# CoinLogger.net
KiCad netlist of a schematic drawn in EAGLE
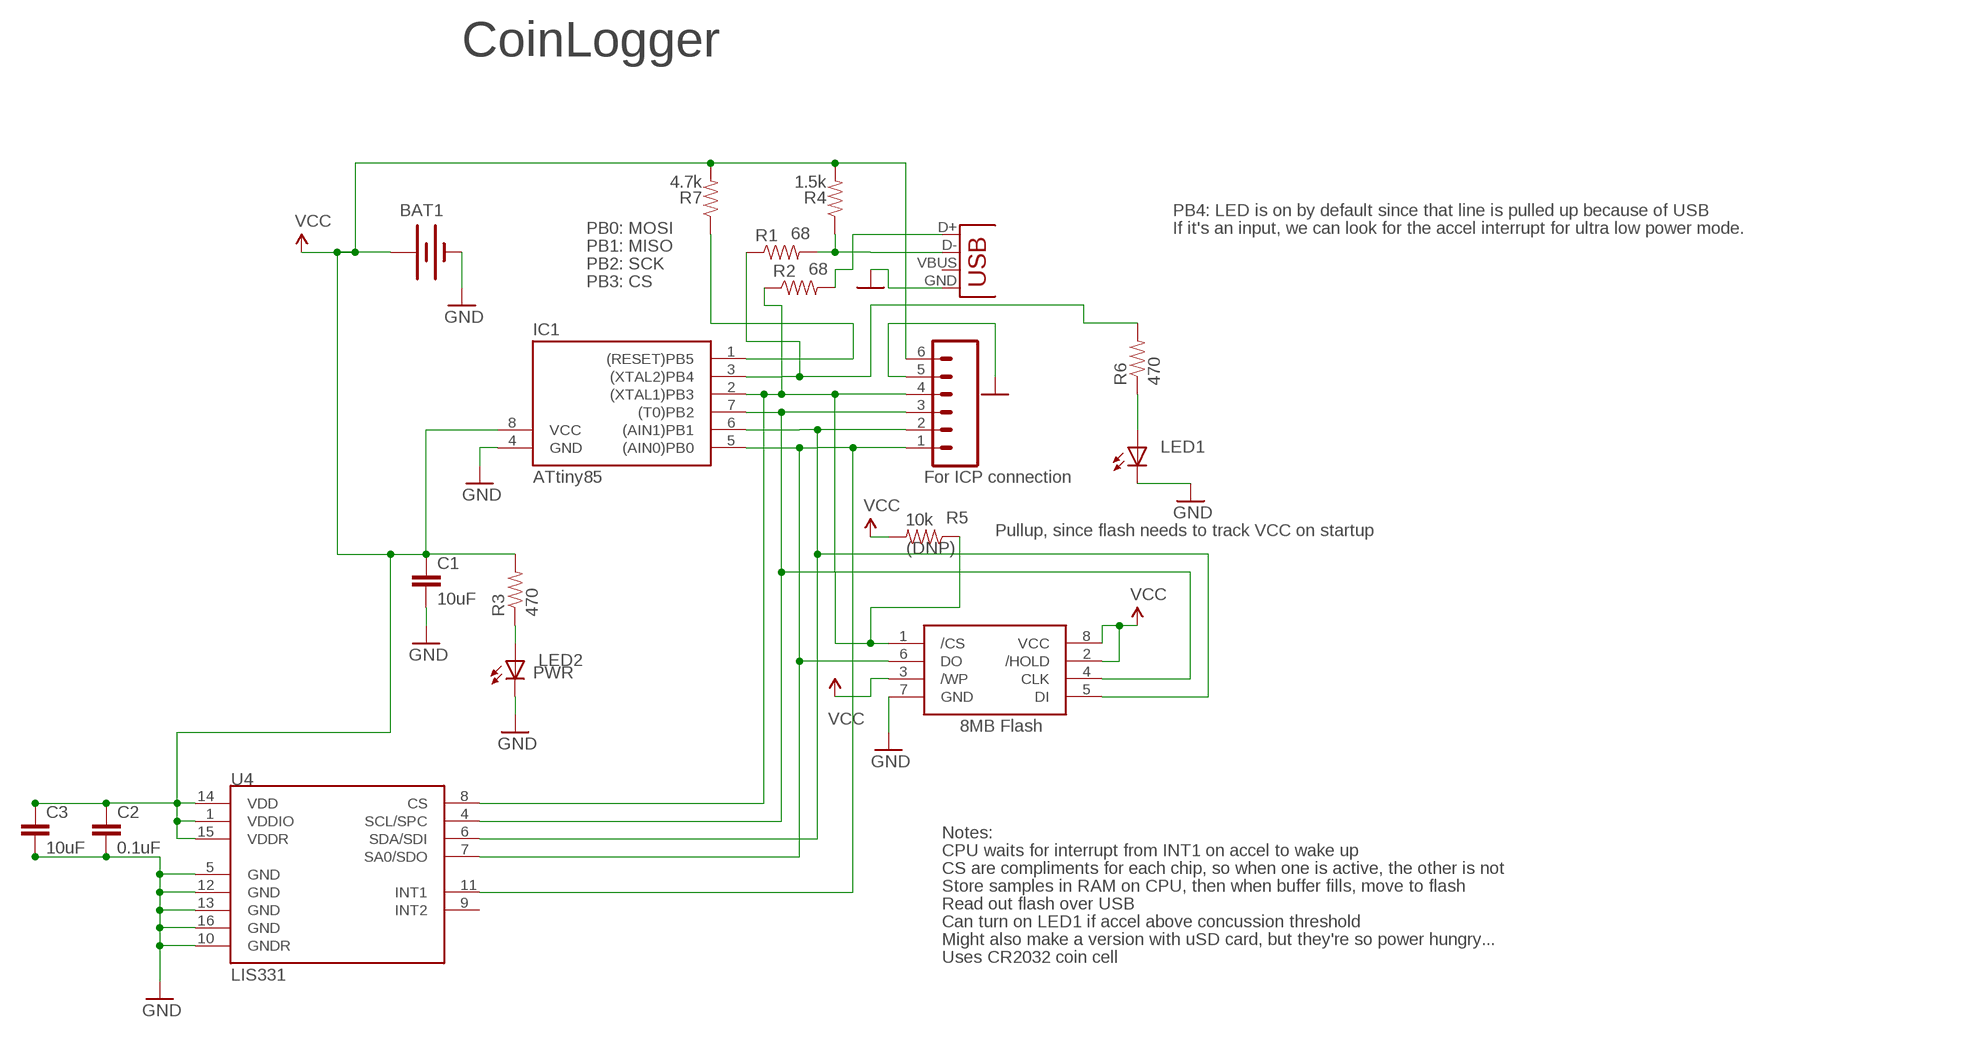
[diagram p0: schematic, sheet 1]

(export (version "E")
  (design (tool "Eeschema 10.0.6"))
  (components
    (comp (ref "BAT1")
      (value "BATTERY20SMD")
      (footprint "eagle-import:BATTCON_20MM")
      (libsource (lib "eagle-import") (part "BATTERY20SMD"))
    )
    (comp (ref "C1")
      (value "10uF")
      (footprint "eagle-import:0402-CAP")
      (libsource (lib "eagle-import") (part "CAP0402-CAP"))
    )
    (comp (ref "C2")
      (value "0.1uF")
      (footprint "eagle-import:0402-CAP")
      (libsource (lib "eagle-import") (part "CAP0402-CAP"))
    )
    (comp (ref "C3")
      (value "10uF")
      (footprint "eagle-import:0402-CAP")
      (libsource (lib "eagle-import") (part "CAP0402-CAP"))
    )
    (comp (ref "IC1")
      (value "TINY11S")
      (footprint "eagle-import:SOIC8")
      (libsource (lib "eagle-import") (part "TINY11S"))
    )
    (comp (ref "JP2")
      (value "M061X06-SMD_EDGE_FEMALE")
      (footprint "eagle-import:1X06-SMD_EDGE")
      (libsource (lib "eagle-import") (part "M061X06-SMD_EDGE_FEMALE"))
    )
    (comp (ref "LED1")
      (value "LED0603")
      (footprint "eagle-import:LED-0603")
      (libsource (lib "eagle-import") (part "LED0603"))
    )
    (comp (ref "LED2")
      (value "LED0603")
      (footprint "eagle-import:LED-0603")
      (libsource (lib "eagle-import") (part "LED0603"))
    )
    (comp (ref "R1")
      (value "68")
      (footprint "eagle-import:0402-RES")
      (libsource (lib "eagle-import") (part "RESISTOR0402-RES"))
    )
    (comp (ref "R2")
      (value "68")
      (footprint "eagle-import:0402-RES")
      (libsource (lib "eagle-import") (part "RESISTOR0402-RES"))
    )
    (comp (ref "R3")
      (value "470")
      (footprint "eagle-import:0402-RES")
      (libsource (lib "eagle-import") (part "RESISTOR0402-RES"))
    )
    (comp (ref "R4")
      (value "1.5k")
      (footprint "eagle-import:0402-RES")
      (libsource (lib "eagle-import") (part "RESISTOR0402-RES"))
    )
    (comp (ref "R5")
      (value "10k")
      (footprint "eagle-import:0402-RES")
      (libsource (lib "eagle-import") (part "RESISTOR0402-RES"))
    )
    (comp (ref "R6")
      (value "470")
      (footprint "eagle-import:0402-RES")
      (libsource (lib "eagle-import") (part "RESISTOR0402-RES"))
    )
    (comp (ref "R7")
      (value "4.7k")
      (footprint "eagle-import:0402-RES")
      (libsource (lib "eagle-import") (part "RESISTOR0402-RES"))
    )
    (comp (ref "U$1")
      (value "W25Q80BV")
      (footprint "eagle-import:SOIC8")
      (libsource (lib "eagle-import") (part "W25Q80BV"))
    )
    (comp (ref "U4")
      (value "LIS331")
      (footprint "eagle-import:LGA16-3MM")
      (libsource (lib "eagle-import") (part "LIS331"))
    )
    (comp (ref "X1")
      (value "USB-MICROB")
      (footprint "eagle-import:USB-MICROB")
      (libsource (lib "eagle-import") (part "USB-MICROB"))
    )
  )
  (nets
    (net (code "1") (name "GND") (class "Default")
      (node (ref "BAT1") (pin "2") (pinfunction "-_2") (pintype "power_in"))
      (node (ref "C1") (pin "2") (pinfunction "2_2") (pintype "passive"))
      (node (ref "C2") (pin "2") (pinfunction "2_2") (pintype "passive"))
      (node (ref "C3") (pin "2") (pinfunction "2_2") (pintype "passive"))
      (node (ref "IC1") (pin "4") (pinfunction "GND_4") (pintype "power_in"))
      (node (ref "JP2") (pin "5") (pinfunction "5_5") (pintype "passive"))
      (node (ref "LED1") (pin "C") (pinfunction "C_C") (pintype "passive"))
      (node (ref "LED2") (pin "C") (pinfunction "C_C") (pintype "passive"))
      (node (ref "U$1") (pin "7") (pinfunction "GND_7") (pintype "bidirectional"))
      (node (ref "U4") (pin "10") (pinfunction "GNDR_10") (pintype "bidirectional"))
      (node (ref "U4") (pin "12") (pinfunction "GND_12") (pintype "bidirectional"))
      (node (ref "U4") (pin "13") (pinfunction "GND_13") (pintype "bidirectional"))
      (node (ref "U4") (pin "16") (pinfunction "GND_16") (pintype "bidirectional"))
      (node (ref "U4") (pin "5") (pinfunction "GND_5") (pintype "bidirectional"))
      (node (ref "X1") (pin "GND") (pinfunction "GND_GND") (pintype "bidirectional"))
    )
    (net (code "2") (name "Net-(IC1-(AIN0)PB0)") (class "Default")
      (node (ref "IC1") (pin "5") (pinfunction "(AIN0)PB0_5") (pintype "bidirectional"))
      (node (ref "JP2") (pin "1") (pinfunction "1_1") (pintype "passive"))
      (node (ref "U$1") (pin "6") (pinfunction "DO_6") (pintype "bidirectional"))
      (node (ref "U4") (pin "11") (pinfunction "INT1_11") (pintype "bidirectional"))
      (node (ref "U4") (pin "7") (pinfunction "SA0/SDO_7") (pintype "bidirectional"))
    )
    (net (code "3") (name "Net-(IC1-(AIN1)PB1)") (class "Default")
      (node (ref "IC1") (pin "6") (pinfunction "(AIN1)PB1_6") (pintype "bidirectional"))
      (node (ref "JP2") (pin "2") (pinfunction "2_2") (pintype "passive"))
      (node (ref "U$1") (pin "5") (pinfunction "DI_5") (pintype "bidirectional"))
      (node (ref "U4") (pin "6") (pinfunction "SDA/SDI_6") (pintype "bidirectional"))
    )
    (net (code "4") (name "Net-(IC1-(RESET)PB5)") (class "Default")
      (node (ref "IC1") (pin "1") (pinfunction "(RESET)PB5_1") (pintype "bidirectional"))
      (node (ref "R7") (pin "1") (pinfunction "1_1") (pintype "passive"))
    )
    (net (code "5") (name "Net-(IC1-(T0)PB2)") (class "Default")
      (node (ref "IC1") (pin "7") (pinfunction "(T0)PB2_7") (pintype "bidirectional"))
      (node (ref "JP2") (pin "3") (pinfunction "3_3") (pintype "passive"))
      (node (ref "U$1") (pin "4") (pinfunction "CLK_4") (pintype "bidirectional"))
      (node (ref "U4") (pin "4") (pinfunction "SCL/SPC_4") (pintype "bidirectional"))
    )
    (net (code "6") (name "Net-(IC1-(XTAL1)PB3)") (class "Default")
      (node (ref "IC1") (pin "2") (pinfunction "(XTAL1)PB3_2") (pintype "bidirectional"))
      (node (ref "JP2") (pin "4") (pinfunction "4_4") (pintype "passive"))
      (node (ref "R2") (pin "1") (pinfunction "1_1") (pintype "passive"))
      (node (ref "R5") (pin "1") (pinfunction "1_1") (pintype "passive"))
      (node (ref "U$1") (pin "1") (pinfunction "/CS_1") (pintype "bidirectional"))
      (node (ref "U4") (pin "8") (pinfunction "CS_8") (pintype "bidirectional"))
    )
    (net (code "7") (name "Net-(IC1-(XTAL2)PB4)") (class "Default")
      (node (ref "IC1") (pin "3") (pinfunction "(XTAL2)PB4_3") (pintype "bidirectional"))
      (node (ref "R1") (pin "1") (pinfunction "1_1") (pintype "passive"))
      (node (ref "R6") (pin "2") (pinfunction "2_2") (pintype "passive"))
    )
    (net (code "8") (name "Net-(LED1-PadA)") (class "Default")
      (node (ref "LED1") (pin "A") (pinfunction "A_A") (pintype "passive"))
      (node (ref "R6") (pin "1") (pinfunction "1_1") (pintype "passive"))
    )
    (net (code "9") (name "Net-(LED2-PadA)") (class "Default")
      (node (ref "LED2") (pin "A") (pinfunction "A_A") (pintype "passive"))
      (node (ref "R3") (pin "1") (pinfunction "1_1") (pintype "passive"))
    )
    (net (code "10") (name "Net-(R1-Pad2)") (class "Default")
      (node (ref "R1") (pin "2") (pinfunction "2_2") (pintype "passive"))
      (node (ref "R4") (pin "1") (pinfunction "1_1") (pintype "passive"))
      (node (ref "X1") (pin "D-") (pinfunction "D-_D-") (pintype "bidirectional"))
    )
    (net (code "11") (name "Net-(R2-Pad2)") (class "Default")
      (node (ref "R2") (pin "2") (pinfunction "2_2") (pintype "passive"))
      (node (ref "X1") (pin "D+") (pinfunction "D+_D+") (pintype "bidirectional"))
    )
    (net (code "12") (name "VCC") (class "Default")
      (node (ref "BAT1") (pin "1") (pinfunction "+_1") (pintype "power_in"))
      (node (ref "C1") (pin "1") (pinfunction "1_1") (pintype "passive"))
      (node (ref "C2") (pin "1") (pinfunction "1_1") (pintype "passive"))
      (node (ref "C3") (pin "1") (pinfunction "1_1") (pintype "passive"))
      (node (ref "IC1") (pin "8") (pinfunction "VCC_8") (pintype "power_in"))
      (node (ref "JP2") (pin "6") (pinfunction "6_6") (pintype "passive"))
      (node (ref "R3") (pin "2") (pinfunction "2_2") (pintype "passive"))
      (node (ref "R4") (pin "2") (pinfunction "2_2") (pintype "passive"))
      (node (ref "R5") (pin "2") (pinfunction "2_2") (pintype "passive"))
      (node (ref "R7") (pin "2") (pinfunction "2_2") (pintype "passive"))
      (node (ref "U$1") (pin "2") (pinfunction "/HOLD_2") (pintype "bidirectional"))
      (node (ref "U$1") (pin "3") (pinfunction "/WP_3") (pintype "bidirectional"))
      (node (ref "U$1") (pin "8") (pinfunction "VCC_8") (pintype "bidirectional"))
      (node (ref "U4") (pin "1") (pinfunction "VDDIO_1") (pintype "bidirectional"))
      (node (ref "U4") (pin "14") (pinfunction "VDD_14") (pintype "bidirectional"))
      (node (ref "U4") (pin "15") (pinfunction "VDDR_15") (pintype "bidirectional"))
    )
    (net (code "13") (name "unconnected-(U4-INT2-Pad9)") (class "Default")
      (node (ref "U4") (pin "9") (pinfunction "INT2_9") (pintype "bidirectional"))
    )
    (net (code "14") (name "unconnected-(X1-PadVBUS)") (class "Default")
      (node (ref "X1") (pin "VBUS") (pinfunction "VBUS_VBUS") (pintype "bidirectional"))
    )
  )
)
